# WaterLevel-STM8-V1.net
KiCad netlist of a schematic drawn in EAGLE
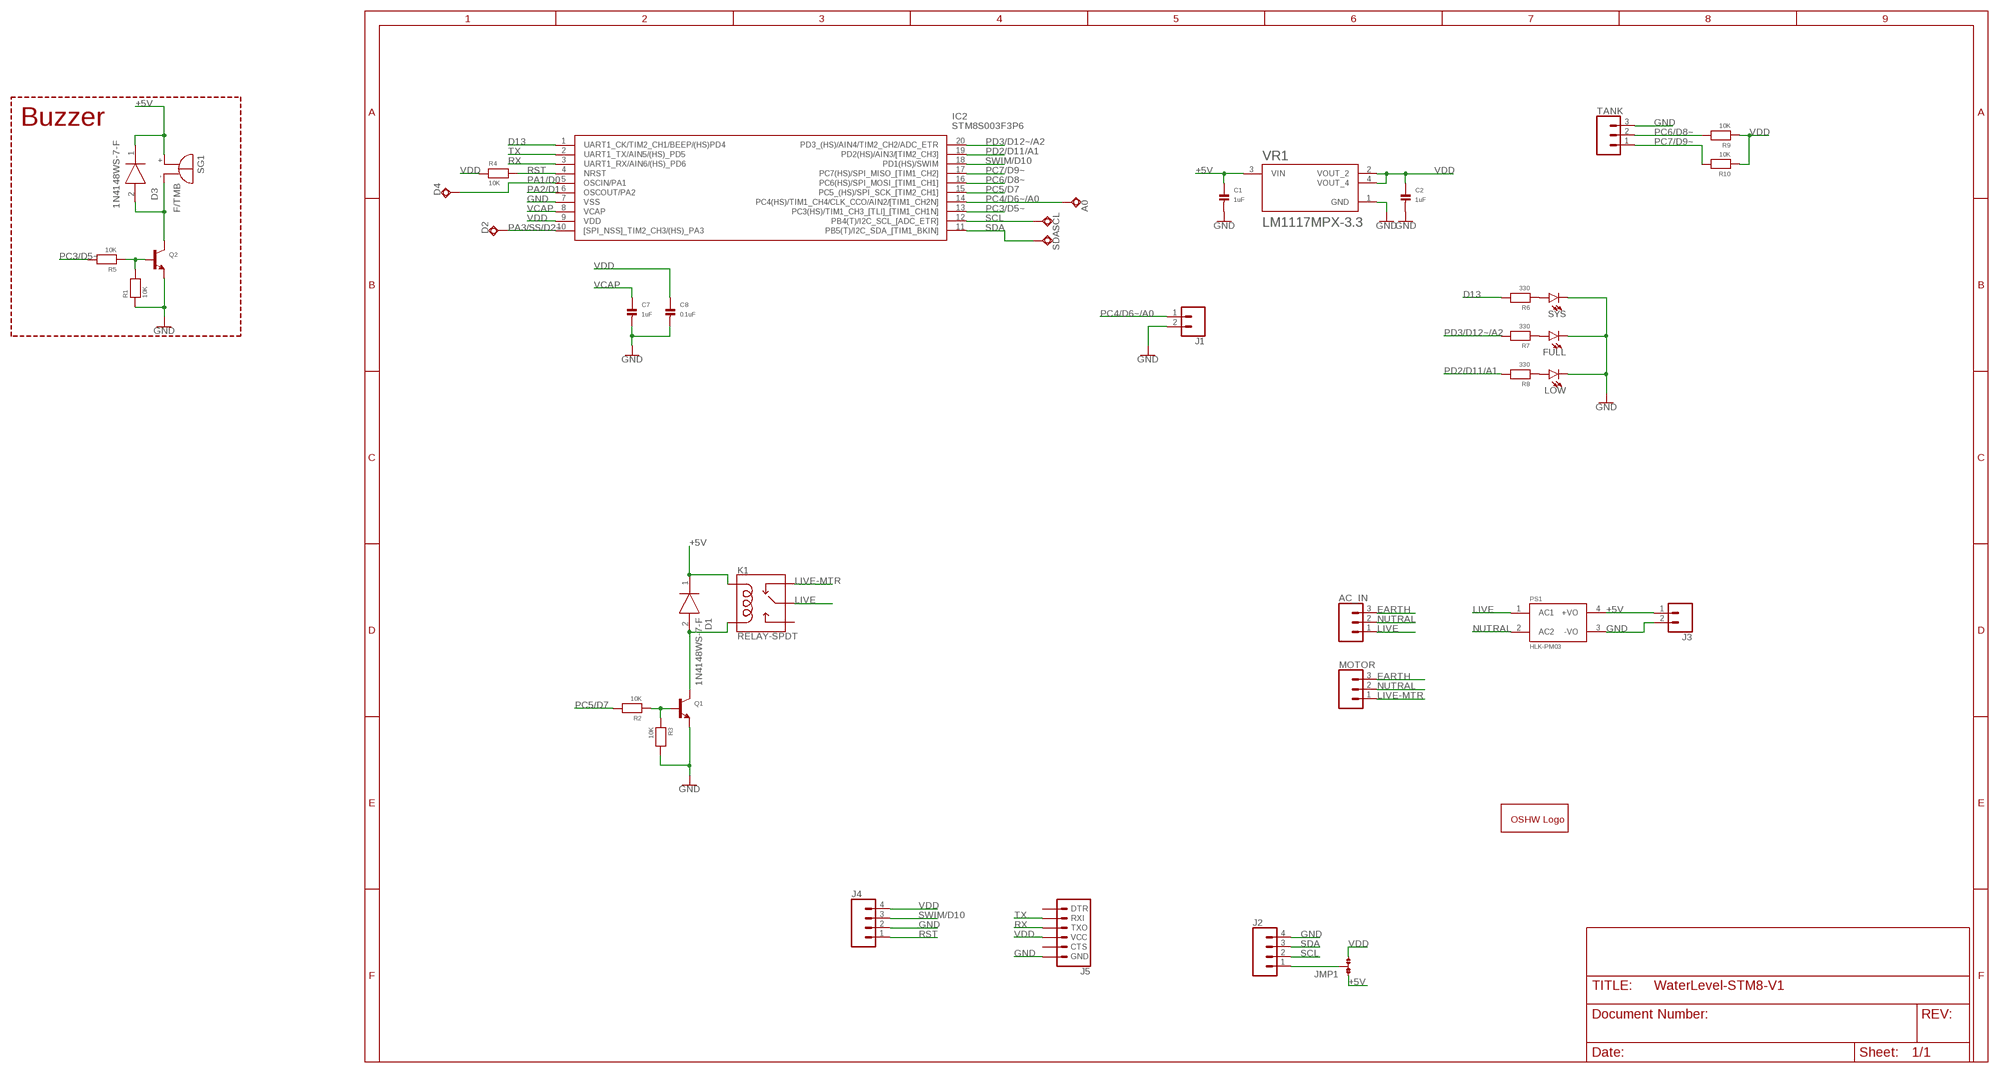
[diagram p0: schematic, sheet 1]

(export (version "E")
  (design (tool "Eeschema 10.0.6"))
  (components
    (comp (ref "A0")
      (value "TPSQTP20R")
      (footprint "eagle-import:TP20R")
      (libsource (lib "eagle-import") (part "TPSQTP20R"))
    )
    (comp (ref "AC_IN")
      (value "SCREW-CONN_03-SCREW-5MM")
      (footprint "eagle-import:SCREWTERMINAL-5MM-3")
      (libsource (lib "eagle-import") (part "SCREW-CONN_03-SCREW-5MM"))
    )
    (comp (ref "C1")
      (value "1uF")
      (footprint "eagle-import:C0805")
      (libsource (lib "eagle-import") (part "CAP_CERAMIC0805"))
    )
    (comp (ref "C2")
      (value "1uF")
      (footprint "eagle-import:C0805")
      (libsource (lib "eagle-import") (part "CAP_CERAMIC0805"))
    )
    (comp (ref "C7")
      (value "1uF")
      (footprint "eagle-import:C0805")
      (libsource (lib "eagle-import") (part "CAP_CERAMIC0805"))
    )
    (comp (ref "C8")
      (value "0.1uF")
      (footprint "eagle-import:C0805")
      (libsource (lib "eagle-import") (part "CAP_CERAMIC0805"))
    )
    (comp (ref "D1")
      (value "1N4148WS-7-F")
      (footprint "eagle-import:SOD2513X120N")
      (fields (field (name "MOUSER_PART_NUMBER") "621-1N4148WS-F"))
      (libsource (lib "eagle-import") (part "1N4148WS-7-F"))
    )
    (comp (ref "D2")
      (value "TPSQTP20R")
      (footprint "eagle-import:TP20R")
      (libsource (lib "eagle-import") (part "TPSQTP20R"))
    )
    (comp (ref "D3")
      (value "1N4148WS-7-F")
      (footprint "eagle-import:SOD2513X120N")
      (fields (field (name "MOUSER_PART_NUMBER") "621-1N4148WS-F"))
      (libsource (lib "eagle-import") (part "1N4148WS-7-F"))
    )
    (comp (ref "D4")
      (value "TPSQTP20R")
      (footprint "eagle-import:TP20R")
      (libsource (lib "eagle-import") (part "TPSQTP20R"))
    )
    (comp (ref "FULL")
      (value "LED-5MM-REC5MM")
      (footprint "eagle-import:LED_5MM")
      (libsource (lib "eagle-import") (part "LED-5MM-REC5MM"))
    )
    (comp (ref "GOLD_ORB_SM1")
      (value "OSHWLOGOLOGO16MM")
      (footprint "eagle-import:OSHW_16MM")
      (libsource (lib "eagle-import") (part "OSHWLOGOLOGO16MM"))
    )
    (comp (ref "IC2")
      (value "STM8S003F3P6")
      (footprint "eagle-import:SOP65P640X120-20N")
      (fields (field (name "MOUSER_PART_NUMBER") "511-STM8S003F3P6"))
      (libsource (lib "eagle-import") (part "STM8S003F3P6"))
    )
    (comp (ref "J1")
      (value "2PIN-2.54MM-POLARPOLAR")
      (footprint "eagle-import:MOLEX-1X2")
      (libsource (lib "eagle-import") (part "2PIN-2.54MM-POLARPOLAR"))
    )
    (comp (ref "J2")
      (value "CONN_04PTH")
      (footprint "eagle-import:1X04")
      (libsource (lib "eagle-import") (part "CONN_04PTH"))
    )
    (comp (ref "J3")
      (value "2PIN-2.54MM-POLARPOLAR")
      (footprint "eagle-import:MOLEX-1X2")
      (libsource (lib "eagle-import") (part "2PIN-2.54MM-POLARPOLAR"))
    )
    (comp (ref "J4")
      (value "CONN_04PTH")
      (footprint "eagle-import:1X04")
      (libsource (lib "eagle-import") (part "CONN_04PTH"))
    )
    (comp (ref "J5")
      (value "6_PIN_SERIAL_TARGETSILK")
      (footprint "eagle-import:6_PIN_SERIAL_TARGET_SIDE_W_SILK")
      (libsource (lib "eagle-import") (part "6_PIN_SERIAL_TARGETSILK"))
    )
    (comp (ref "JMP1")
      (value "JMP-3-NO")
      (footprint "eagle-import:JMP-3-NO")
      (libsource (lib "eagle-import") (part "JMP-3-NO"))
    )
    (comp (ref "K1")
      (value "RELAY-SPDT")
      (footprint "eagle-import:RELAY_G5LE")
      (libsource (lib "eagle-import") (part "RELAY-SPDT"))
    )
    (comp (ref "LOW")
      (value "LED-5MM-REC5MM")
      (footprint "eagle-import:LED_5MM")
      (libsource (lib "eagle-import") (part "LED-5MM-REC5MM"))
    )
    (comp (ref "MOTOR")
      (value "SCREW-CONN_03-SCREW-5MM")
      (footprint "eagle-import:SCREWTERMINAL-5MM-3")
      (libsource (lib "eagle-import") (part "SCREW-CONN_03-SCREW-5MM"))
    )
    (comp (ref "PS1")
      (value "HLK-PM03")
      (footprint "eagle-import:CONV_HLK-PM03")
      (fields (field (name "MF") "Hi-link"))
      (libsource (lib "eagle-import") (part "HLK-PM03"))
    )
    (comp (ref "Q1")
      (value "TRANSISTOR_NPNWIDE")
      (footprint "eagle-import:SOT23-WIDE")
      (libsource (lib "eagle-import") (part "TRANSISTOR_NPNWIDE"))
    )
    (comp (ref "Q2")
      (value "TRANSISTOR_NPNWIDE")
      (footprint "eagle-import:SOT23-WIDE")
      (libsource (lib "eagle-import") (part "TRANSISTOR_NPNWIDE"))
    )
    (comp (ref "R1")
      (value "10K")
      (footprint "eagle-import:R0805")
      (libsource (lib "eagle-import") (part "RESISTOR0805"))
    )
    (comp (ref "R2")
      (value "10K")
      (footprint "eagle-import:R0805")
      (libsource (lib "eagle-import") (part "RESISTOR0805"))
    )
    (comp (ref "R3")
      (value "10K")
      (footprint "eagle-import:R0805")
      (libsource (lib "eagle-import") (part "RESISTOR0805"))
    )
    (comp (ref "R4")
      (value "10K")
      (footprint "eagle-import:R0805")
      (libsource (lib "eagle-import") (part "RESISTOR0805"))
    )
    (comp (ref "R5")
      (value "10K")
      (footprint "eagle-import:R0805")
      (libsource (lib "eagle-import") (part "RESISTOR0805"))
    )
    (comp (ref "R6")
      (value "330")
      (footprint "eagle-import:R0805")
      (libsource (lib "eagle-import") (part "RESISTOR0805"))
    )
    (comp (ref "R7")
      (value "330")
      (footprint "eagle-import:R0805")
      (libsource (lib "eagle-import") (part "RESISTOR0805"))
    )
    (comp (ref "R8")
      (value "330")
      (footprint "eagle-import:R0805")
      (libsource (lib "eagle-import") (part "RESISTOR0805"))
    )
    (comp (ref "R9")
      (value "10K")
      (footprint "eagle-import:R0805")
      (libsource (lib "eagle-import") (part "RESISTOR0805"))
    )
    (comp (ref "R10")
      (value "10K")
      (footprint "eagle-import:R0805")
      (libsource (lib "eagle-import") (part "RESISTOR0805"))
    )
    (comp (ref "SCL")
      (value "TPSQTP20R")
      (footprint "eagle-import:TP20R")
      (libsource (lib "eagle-import") (part "TPSQTP20R"))
    )
    (comp (ref "SDA")
      (value "TPSQTP20R")
      (footprint "eagle-import:TP20R")
      (libsource (lib "eagle-import") (part "TPSQTP20R"))
    )
    (comp (ref "SG1")
      (value "F/TMB")
      (footprint "eagle-import:F_TMB")
      (libsource (lib "eagle-import") (part "F/TMB"))
    )
    (comp (ref "SYS")
      (value "LED-5MM-REC5MM")
      (footprint "eagle-import:LED_5MM")
      (libsource (lib "eagle-import") (part "LED-5MM-REC5MM"))
    )
    (comp (ref "TANK")
      (value "SCREW-CONN_03-SCREW-5MM")
      (footprint "eagle-import:SCREWTERMINAL-5MM-3")
      (libsource (lib "eagle-import") (part "SCREW-CONN_03-SCREW-5MM"))
    )
    (comp (ref "VR1")
      (value "LM1117MPX-3.3")
      (footprint "eagle-import:VREG_LM1117MPX-3.3")
      (fields (field (name "MF") "Texas Instruments"))
      (libsource (lib "eagle-import") (part "LM1117MPX-3.3"))
    )
  )
  (nets
    (net (code "1") (name "/+5V") (class "Default")
      (node (ref "C1") (pin "1") (pinfunction "P$1_1") (pintype "passive"))
      (node (ref "D1") (pin "1") (pinfunction "K_1") (pintype "bidirectional"))
      (node (ref "D3") (pin "1") (pinfunction "K_1") (pintype "bidirectional"))
      (node (ref "J3") (pin "1") (pinfunction "1_1") (pintype "passive"))
      (node (ref "JMP1") (pin "1") (pinfunction "1_1") (pintype "passive"))
      (node (ref "K1") (pin "2") (pinfunction "COIL1_2") (pintype "bidirectional"))
      (node (ref "PS1") (pin "4") (pinfunction "+VO_4") (pintype "output"))
      (node (ref "SG1") (pin "+") (pinfunction "+_+") (pintype "passive"))
      (node (ref "VR1") (pin "3") (pinfunction "VIN_3") (pintype "input"))
    )
    (net (code "2") (name "/D13") (class "Default")
      (node (ref "IC2") (pin "1") (pinfunction "UART1_CK/TIM2_CH1/BEEP/(HS)PD4_1") (pintype "bidirectional"))
      (node (ref "R6") (pin "2") (pinfunction "2_2") (pintype "passive"))
    )
    (net (code "3") (name "/EARTH") (class "Default")
      (node (ref "AC_IN") (pin "3") (pinfunction "3_3") (pintype "passive"))
      (node (ref "MOTOR") (pin "3") (pinfunction "3_3") (pintype "passive"))
    )
    (net (code "4") (name "/LIVE") (class "Default")
      (node (ref "AC_IN") (pin "1") (pinfunction "1_1") (pintype "passive"))
      (node (ref "K1") (pin "1") (pinfunction "MAIN_1") (pintype "bidirectional"))
      (node (ref "PS1") (pin "1") (pinfunction "AC1_1") (pintype "input"))
    )
    (net (code "5") (name "/LIVE-MTR") (class "Default")
      (node (ref "K1") (pin "4") (pinfunction "NC_4") (pintype "bidirectional"))
      (node (ref "MOTOR") (pin "1") (pinfunction "1_1") (pintype "passive"))
    )
    (net (code "6") (name "/NUTRAL") (class "Default")
      (node (ref "AC_IN") (pin "2") (pinfunction "2_2") (pintype "passive"))
      (node (ref "MOTOR") (pin "2") (pinfunction "2_2") (pintype "passive"))
      (node (ref "PS1") (pin "2") (pinfunction "AC2_2") (pintype "input"))
    )
    (net (code "7") (name "/PA1{slash}D0") (class "Default")
      (node (ref "D4") (pin "TP") (pinfunction "TP_TP") (pintype "input"))
      (node (ref "IC2") (pin "5") (pinfunction "OSCIN/PA1_5") (pintype "input"))
    )
    (net (code "8") (name "/PA2{slash}D1") (class "Default")
      (node (ref "IC2") (pin "6") (pinfunction "OSCOUT/PA2_6") (pintype "output"))
    )
    (net (code "9") (name "/PA3{slash}SS{slash}D2~{}") (class "Default")
      (node (ref "D2") (pin "TP") (pinfunction "TP_TP") (pintype "input"))
      (node (ref "IC2") (pin "10") (pinfunction "[SPI_NSS]_TIM2_CH3/(HS)_PA3_10") (pintype "bidirectional"))
    )
    (net (code "10") (name "/PC3{slash}D5~{}") (class "Default")
      (node (ref "IC2") (pin "13") (pinfunction "PC3(HS)/TIM1_CH3_[TLI]_[TIM1_CH1N]_13") (pintype "bidirectional"))
      (node (ref "R5") (pin "2") (pinfunction "2_2") (pintype "passive"))
    )
    (net (code "11") (name "/PC4{slash}D6~{{slash}A0}") (class "Default")
      (node (ref "A0") (pin "TP") (pinfunction "TP_TP") (pintype "input"))
      (node (ref "IC2") (pin "14") (pinfunction "PC4(HS)/TIM1_CH4/CLK_CCO/AIN2/[TIM1_CH2N]_14") (pintype "input"))
      (node (ref "J1") (pin "1") (pinfunction "1_1") (pintype "passive"))
    )
    (net (code "12") (name "/PC5{slash}D7") (class "Default")
      (node (ref "IC2") (pin "15") (pinfunction "PC5_(HS)/SPI_SCK_[TIM2_CH1]_15") (pintype "bidirectional"))
      (node (ref "R2") (pin "2") (pinfunction "2_2") (pintype "passive"))
    )
    (net (code "13") (name "/PC6{slash}D8~{}") (class "Default")
      (node (ref "IC2") (pin "16") (pinfunction "PC6(HS)/SPI_MOSI_[TIM1_CH1]_16") (pintype "bidirectional"))
      (node (ref "R9") (pin "2") (pinfunction "2_2") (pintype "passive"))
      (node (ref "TANK") (pin "2") (pinfunction "2_2") (pintype "passive"))
    )
    (net (code "14") (name "/PC7{slash}D9~{}") (class "Default")
      (node (ref "IC2") (pin "17") (pinfunction "PC7(HS)/SPI_MISO_[TIM1_CH2]_17") (pintype "bidirectional"))
      (node (ref "R10") (pin "2") (pinfunction "2_2") (pintype "passive"))
      (node (ref "TANK") (pin "1") (pinfunction "1_1") (pintype "passive"))
    )
    (net (code "15") (name "/PD2{slash}D11{slash}A1") (class "Default")
      (node (ref "IC2") (pin "19") (pinfunction "PD2(HS)/AIN3/[TIM2_CH3]_19") (pintype "input"))
      (node (ref "R8") (pin "2") (pinfunction "2_2") (pintype "passive"))
    )
    (net (code "16") (name "/PD3{slash}D12~{{slash}A2}") (class "Default")
      (node (ref "IC2") (pin "20") (pinfunction "PD3_(HS)/AIN4/TIM2_CH2/ADC_ETR_20") (pintype "input"))
      (node (ref "R7") (pin "2") (pinfunction "2_2") (pintype "passive"))
    )
    (net (code "17") (name "/RST") (class "Default")
      (node (ref "IC2") (pin "4") (pinfunction "NRST_4") (pintype "input"))
      (node (ref "J4") (pin "1") (pinfunction "1_1") (pintype "passive"))
      (node (ref "R4") (pin "2") (pinfunction "2_2") (pintype "passive"))
    )
    (net (code "18") (name "/RX") (class "Default")
      (node (ref "IC2") (pin "3") (pinfunction "UART1_RX/AIN6/(HS)_PD6_3") (pintype "input"))
      (node (ref "J5") (pin "P$2") (pinfunction "TXO_P$2") (pintype "passive"))
    )
    (net (code "19") (name "/SCL") (class "Default")
      (node (ref "IC2") (pin "12") (pinfunction "PB4(T)/I2C_SCL_[ADC_ETR]_12") (pintype "bidirectional"))
      (node (ref "J2") (pin "2") (pinfunction "2_2") (pintype "passive"))
      (node (ref "SCL") (pin "TP") (pinfunction "TP_TP") (pintype "input"))
    )
    (net (code "20") (name "/SDA") (class "Default")
      (node (ref "IC2") (pin "11") (pinfunction "PB5(T)/I2C_SDA_[TIM1_BKIN]_11") (pintype "input"))
      (node (ref "J2") (pin "3") (pinfunction "3_3") (pintype "passive"))
      (node (ref "SDA") (pin "TP") (pinfunction "TP_TP") (pintype "input"))
    )
    (net (code "21") (name "/SWIM{slash}D10") (class "Default")
      (node (ref "IC2") (pin "18") (pinfunction "PD1(HS)/SWIM_18") (pintype "bidirectional"))
      (node (ref "J4") (pin "3") (pinfunction "3_3") (pintype "passive"))
    )
    (net (code "22") (name "/TX") (class "Default")
      (node (ref "IC2") (pin "2") (pinfunction "UART1_TX/AIN5/(HS)_PD5_2") (pintype "input"))
      (node (ref "J5") (pin "P$3") (pinfunction "RXI_P$3") (pintype "passive"))
    )
    (net (code "23") (name "/VCAP") (class "Default")
      (node (ref "C7") (pin "1") (pinfunction "P$1_1") (pintype "passive"))
      (node (ref "IC2") (pin "8") (pinfunction "VCAP_8") (pintype "bidirectional"))
    )
    (net (code "24") (name "/VDD") (class "Default")
      (node (ref "C2") (pin "1") (pinfunction "P$1_1") (pintype "passive"))
      (node (ref "C8") (pin "1") (pinfunction "P$1_1") (pintype "passive"))
      (node (ref "IC2") (pin "9") (pinfunction "VDD_9") (pintype "power_in"))
      (node (ref "J4") (pin "4") (pinfunction "4_4") (pintype "passive"))
      (node (ref "J5") (pin "P$4") (pinfunction "VCC_P$4") (pintype "passive"))
      (node (ref "JMP1") (pin "3") (pinfunction "3_3") (pintype "passive"))
      (node (ref "R10") (pin "1") (pinfunction "1_1") (pintype "passive"))
      (node (ref "R4") (pin "1") (pinfunction "1_1") (pintype "passive"))
      (node (ref "R9") (pin "1") (pinfunction "1_1") (pintype "passive"))
      (node (ref "VR1") (pin "2") (pinfunction "VOUT_2_2") (pintype "output"))
      (node (ref "VR1") (pin "4") (pinfunction "VOUT_4_4") (pintype "output"))
    )
    (net (code "25") (name "GND") (class "Default")
      (node (ref "C1") (pin "2") (pinfunction "P$2_2") (pintype "passive"))
      (node (ref "C2") (pin "2") (pinfunction "P$2_2") (pintype "passive"))
      (node (ref "C7") (pin "2") (pinfunction "P$2_2") (pintype "passive"))
      (node (ref "C8") (pin "2") (pinfunction "P$2_2") (pintype "passive"))
      (node (ref "FULL") (pin "K") (pinfunction "C_K") (pintype "passive"))
      (node (ref "IC2") (pin "7") (pinfunction "VSS_7") (pintype "power_in"))
      (node (ref "J1") (pin "2") (pinfunction "2_2") (pintype "passive"))
      (node (ref "J2") (pin "4") (pinfunction "4_4") (pintype "passive"))
      (node (ref "J3") (pin "2") (pinfunction "2_2") (pintype "passive"))
      (node (ref "J4") (pin "2") (pinfunction "2_2") (pintype "passive"))
      (node (ref "J5") (pin "P$6") (pinfunction "GND_P$6") (pintype "passive"))
      (node (ref "LOW") (pin "K") (pinfunction "C_K") (pintype "passive"))
      (node (ref "PS1") (pin "3") (pinfunction "-VO_3") (pintype "output"))
      (node (ref "Q1") (pin "2") (pinfunction "E_2") (pintype "passive"))
      (node (ref "Q2") (pin "2") (pinfunction "E_2") (pintype "passive"))
      (node (ref "R1") (pin "1") (pinfunction "1_1") (pintype "passive"))
      (node (ref "R3") (pin "2") (pinfunction "2_2") (pintype "passive"))
      (node (ref "SYS") (pin "K") (pinfunction "C_K") (pintype "passive"))
      (node (ref "TANK") (pin "3") (pinfunction "3_3") (pintype "passive"))
      (node (ref "VR1") (pin "1") (pinfunction "GND_1") (pintype "power_in"))
    )
    (net (code "26") (name "Net-(D1-A)") (class "Default")
      (node (ref "D1") (pin "2") (pinfunction "A_2") (pintype "bidirectional"))
      (node (ref "K1") (pin "5") (pinfunction "COIL2_5") (pintype "bidirectional"))
      (node (ref "Q1") (pin "3") (pinfunction "C_3") (pintype "passive"))
    )
    (net (code "27") (name "Net-(D3-A)") (class "Default")
      (node (ref "D3") (pin "2") (pinfunction "A_2") (pintype "bidirectional"))
      (node (ref "Q2") (pin "3") (pinfunction "C_3") (pintype "passive"))
      (node (ref "SG1") (pin "-") (pinfunction "-_-") (pintype "passive"))
    )
    (net (code "28") (name "Net-(FULL-PadA)") (class "Default")
      (node (ref "FULL") (pin "A") (pinfunction "A_A") (pintype "passive"))
      (node (ref "R7") (pin "1") (pinfunction "1_1") (pintype "passive"))
    )
    (net (code "29") (name "Net-(J2-Pad1)") (class "Default")
      (node (ref "J2") (pin "1") (pinfunction "1_1") (pintype "passive"))
      (node (ref "JMP1") (pin "2") (pinfunction "2_2") (pintype "passive"))
    )
    (net (code "30") (name "Net-(LOW-PadA)") (class "Default")
      (node (ref "LOW") (pin "A") (pinfunction "A_A") (pintype "passive"))
      (node (ref "R8") (pin "1") (pinfunction "1_1") (pintype "passive"))
    )
    (net (code "31") (name "Net-(Q1-B)") (class "Default")
      (node (ref "Q1") (pin "1") (pinfunction "B_1") (pintype "passive"))
      (node (ref "R2") (pin "1") (pinfunction "1_1") (pintype "passive"))
      (node (ref "R3") (pin "1") (pinfunction "1_1") (pintype "passive"))
    )
    (net (code "32") (name "Net-(Q2-B)") (class "Default")
      (node (ref "Q2") (pin "1") (pinfunction "B_1") (pintype "passive"))
      (node (ref "R1") (pin "2") (pinfunction "2_2") (pintype "passive"))
      (node (ref "R5") (pin "1") (pinfunction "1_1") (pintype "passive"))
    )
    (net (code "33") (name "Net-(R6-Pad1)") (class "Default")
      (node (ref "R6") (pin "1") (pinfunction "1_1") (pintype "passive"))
      (node (ref "SYS") (pin "A") (pinfunction "A_A") (pintype "passive"))
    )
    (net (code "34") (name "unconnected-(J5-CTS-PadP$5)") (class "Default")
      (node (ref "J5") (pin "P$5") (pinfunction "CTS_P$5") (pintype "passive"))
    )
    (net (code "35") (name "unconnected-(J5-DTR-PadP$1)") (class "Default")
      (node (ref "J5") (pin "P$1") (pinfunction "DTR_P$1") (pintype "passive"))
    )
    (net (code "36") (name "unconnected-(K1-NO-Pad3)") (class "Default")
      (node (ref "K1") (pin "3") (pinfunction "NO_3") (pintype "bidirectional"))
    )
  )
)
